# mm_robot_pcb_v4_1.net
KiCad netlist of a schematic drawn in EAGLE
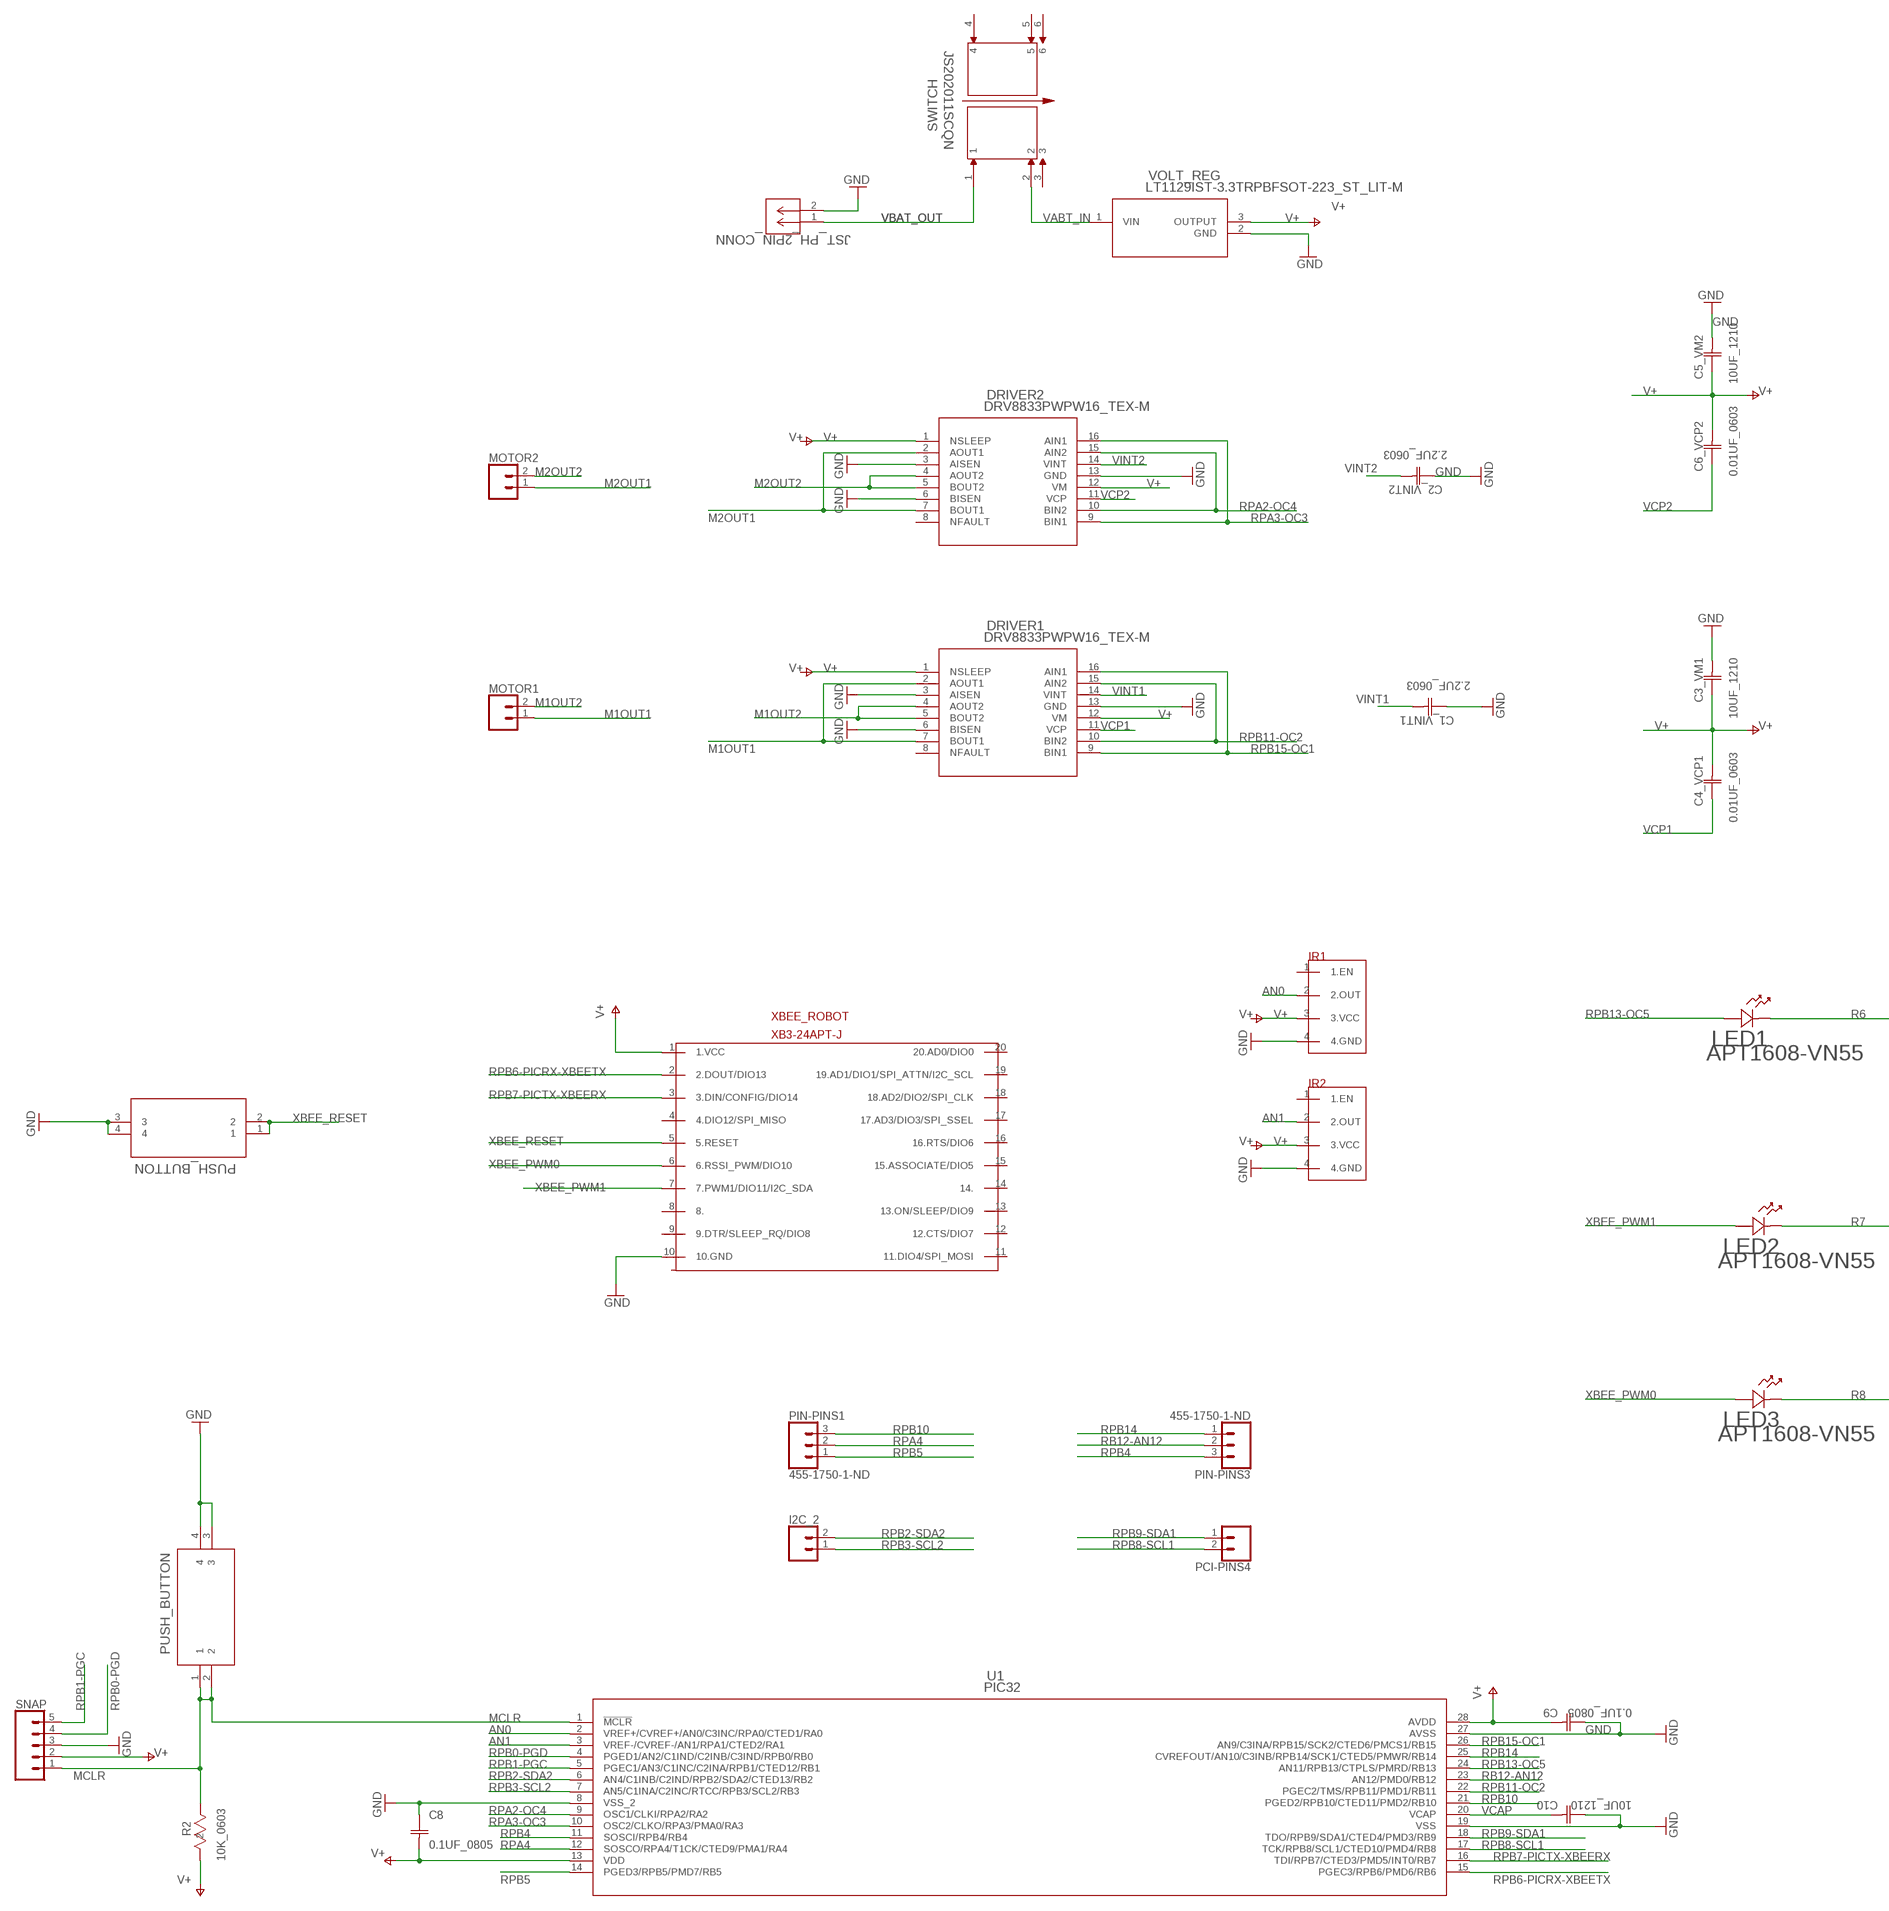
[diagram p0: schematic, sheet 1, part 1 of 2]
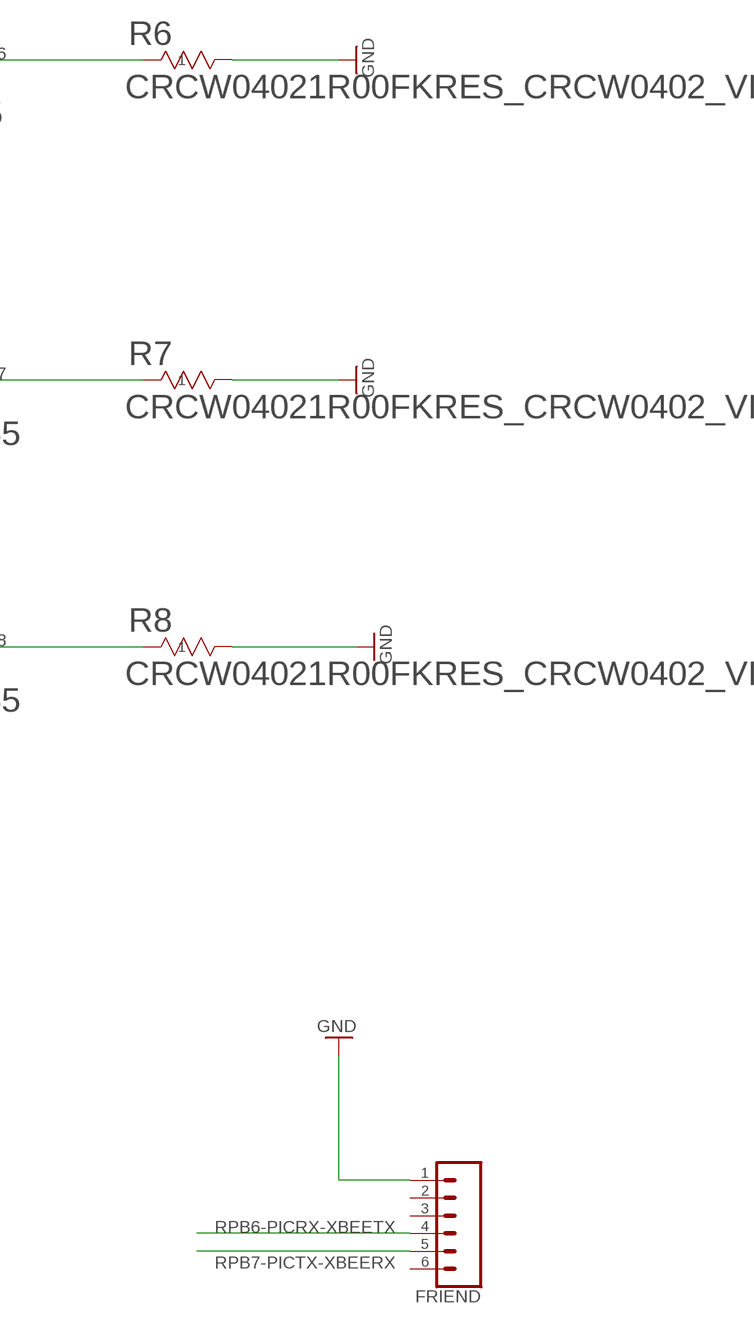
[diagram p1: schematic, sheet 1, part 2 of 2]

(export (version "E")
  (design (tool "Eeschema 10.0.6"))
  (components
    (comp (ref "C1_VINT1")
      (value "2.2UF_0603")
      (footprint "eagle-import:CAP_CL10_SAM-M")
      (fields
        (field (name "MANUFACTURER_PART_NUMBER") "CL10A225KP8NNNC")
        (field (name "COPYRIGHT") "Copyright (C) 2021 Ultra Librarian. All rights reserved.")
      )
      (libsource (lib "eagle-import") (part "CL10A225KP8NNNCCAP_CL10_SAM-M"))
    )
    (comp (ref "C2_VINT2")
      (value "2.2UF_0603")
      (footprint "eagle-import:CAP_CL10_SAM-M")
      (fields
        (field (name "MANUFACTURER_PART_NUMBER") "CL10A225KP8NNNC")
        (field (name "COPYRIGHT") "Copyright (C) 2021 Ultra Librarian. All rights reserved.")
      )
      (libsource (lib "eagle-import") (part "CL10A225KP8NNNCCAP_CL10_SAM-M"))
    )
    (comp (ref "C3_VM1")
      (value "10UF_1210")
      (footprint "eagle-import:CAP_TPS_B_AVX-M")
      (fields
        (field (name "MANUFACTURER_PART_NUMBER") "TPSB106K016R0500")
        (field (name "COPYRIGHT") "Copyright (C) 2021 Ultra Librarian. All rights reserved.")
      )
      (libsource (lib "eagle-import") (part "TPSB106K016R0500CAP_TPS_B_AVX-M"))
    )
    (comp (ref "C4_VCP1")
      (value "0.01UF_0603")
      (footprint "eagle-import:CAP_01UF_0603_X7R_G_AVX")
      (libsource (lib "eagle-import") (part "01UF_CAP"))
    )
    (comp (ref "C5_VM2")
      (value "10UF_1210")
      (footprint "eagle-import:CAP_TPS_B_AVX-M")
      (fields
        (field (name "MANUFACTURER_PART_NUMBER") "TPSB106K016R0500")
        (field (name "COPYRIGHT") "Copyright (C) 2021 Ultra Librarian. All rights reserved.")
      )
      (libsource (lib "eagle-import") (part "TPSB106K016R0500CAP_TPS_B_AVX-M"))
    )
    (comp (ref "C6_VCP2")
      (value "0.01UF_0603")
      (footprint "eagle-import:CAP_01UF_0603_X7R_G_AVX")
      (libsource (lib "eagle-import") (part "01UF_CAP"))
    )
    (comp (ref "C8")
      (value "0.1UF_0805")
      (footprint "eagle-import:CAP_C2012X7R2A104K125AA_TDK-M")
      (fields
        (field (name "MANUFACTURER_PART_NUMBER") "C2012X7R2A104K125AA")
        (field (name "COPYRIGHT") "Copyright (C) 2021 Ultra Librarian. All rights reserved.")
      )
      (libsource (lib "eagle-import") (part "C2012X7R2A104K125AACAP_C2012X7R2A104K125AA_TDK-M"))
    )
    (comp (ref "C9")
      (value "0.1UF_0805")
      (footprint "eagle-import:CAP_C2012X7R2A104K125AA_TDK-M")
      (fields
        (field (name "MANUFACTURER_PART_NUMBER") "C2012X7R2A104K125AA")
        (field (name "COPYRIGHT") "Copyright (C) 2021 Ultra Librarian. All rights reserved.")
      )
      (libsource (lib "eagle-import") (part "C2012X7R2A104K125AACAP_C2012X7R2A104K125AA_TDK-M"))
    )
    (comp (ref "C10")
      (value "10UF_1210")
      (footprint "eagle-import:CAP_TPS_B_AVX-M")
      (fields
        (field (name "MANUFACTURER_PART_NUMBER") "TPSB106K016R0500")
        (field (name "COPYRIGHT") "Copyright (C) 2021 Ultra Librarian. All rights reserved.")
      )
      (libsource (lib "eagle-import") (part "TPSB106K016R0500CAP_TPS_B_AVX-M"))
    )
    (comp (ref "DRIVER1")
      (value "DRV8833PWPW16_TEX-M")
      (footprint "eagle-import:PW16_TEX-M")
      (fields
        (field (name "MANUFACTURER_PART_NUMBER") "DRV8833PW")
        (field (name "COPYRIGHT") "Copyright (C) 2021 Ultra Librarian. All rights reserved.")
      )
      (libsource (lib "eagle-import") (part "DRV8833PWPW16_TEX-M"))
    )
    (comp (ref "DRIVER2")
      (value "DRV8833PWPW16_TEX-M")
      (footprint "eagle-import:PW16_TEX-M")
      (fields
        (field (name "MANUFACTURER_PART_NUMBER") "DRV8833PW")
        (field (name "COPYRIGHT") "Copyright (C) 2021 Ultra Librarian. All rights reserved.")
      )
      (libsource (lib "eagle-import") (part "DRV8833PWPW16_TEX-M"))
    )
    (comp (ref "FRIEND")
      (value "CONN_06NO_SILK_FEMALE_PTH")
      (footprint "eagle-import:1X06_NO_SILK")
      (libsource (lib "eagle-import") (part "CONN_06NO_SILK_FEMALE_PTH"))
    )
    (comp (ref "I2C_2")
      (value "CONN_02")
      (footprint "eagle-import:1X02")
      (libsource (lib "eagle-import") (part "CONN_02"))
    )
    (comp (ref "IR1")
      (value "GP2Y0A60SZLF")
      (footprint "eagle-import:1X04")
      (libsource (lib "eagle-import") (part "GP2Y0A60SZLF"))
    )
    (comp (ref "IR2")
      (value "GP2Y0A60SZLF")
      (footprint "eagle-import:1X04")
      (libsource (lib "eagle-import") (part "GP2Y0A60SZLF"))
    )
    (comp (ref "JST_PH_2PIN_CONN")
      (value "1769")
      (footprint "eagle-import:CONN_1769_ADA")
      (fields (field (name "COPYRIGHT") "Copyright (C) 2021 Ultra Librarian. All rights reserved."))
      (libsource (lib "eagle-import") (part "1769"))
    )
    (comp (ref "LED1")
      (value "APT1608-VN55")
      (footprint "eagle-import:LED_APT1608_KNB")
      (fields (field (name "COPYRIGHT") "Copyright (C) 2021 Ultra Librarian. All rights reserved."))
      (libsource (lib "eagle-import") (part "APT1608-VN55"))
    )
    (comp (ref "LED2")
      (value "APT1608-VN55")
      (footprint "eagle-import:LED_APT1608_KNB")
      (fields (field (name "COPYRIGHT") "Copyright (C) 2021 Ultra Librarian. All rights reserved."))
      (libsource (lib "eagle-import") (part "APT1608-VN55"))
    )
    (comp (ref "LED3")
      (value "APT1608-VN55")
      (footprint "eagle-import:LED_APT1608_KNB")
      (fields (field (name "COPYRIGHT") "Copyright (C) 2021 Ultra Librarian. All rights reserved."))
      (libsource (lib "eagle-import") (part "APT1608-VN55"))
    )
    (comp (ref "MOTOR1")
      (value "CONN_02")
      (footprint "eagle-import:1X02")
      (libsource (lib "eagle-import") (part "CONN_02"))
    )
    (comp (ref "MOTOR2")
      (value "CONN_02")
      (footprint "eagle-import:1X02")
      (libsource (lib "eagle-import") (part "CONN_02"))
    )
    (comp (ref "PCI-PINS4")
      (value "CONN_02")
      (footprint "eagle-import:1X02")
      (libsource (lib "eagle-import") (part "CONN_02"))
    )
    (comp (ref "PIC_PB")
      (value "PUSH_BUTTON")
      (footprint "eagle-import:SMT_FS-M")
      (fields
        (field (name "MANUFACTURER_PART_NUMBER") "PTS526 SK15 SMTR2 LFS")
        (field (name "COPYRIGHT") "Copyright (C) 2021 Ultra Librarian. All rights reserved.")
      )
      (libsource (lib "eagle-import") (part "PTS526_SK15_SMTR2_LFSSMT_FS-M"))
    )
    (comp (ref "PIN-PINS1")
      (value "455-1750-1-ND")
      (footprint "eagle-import:1X03")
      (libsource (lib "eagle-import") (part "CONN_03"))
    )
    (comp (ref "PIN-PINS3")
      (value "455-1750-1-ND")
      (footprint "eagle-import:1X03")
      (libsource (lib "eagle-import") (part "CONN_03"))
    )
    (comp (ref "R2")
      (value "10K_0603")
      (footprint "eagle-import:RES0603_CRG_TYCO_TYC-M")
      (fields
        (field (name "MANUFACTURER_PART_NUMBER") "CRG0603F10K")
        (field (name "COPYRIGHT") "Copyright (C) 2021 Ultra Librarian. All rights reserved.")
      )
      (libsource (lib "eagle-import") (part "CRG0603F10KRES0603_CRG_TYCO_TYC-M"))
    )
    (comp (ref "R6")
      (value "CRCW04021R00FKRES_CRCW0402_VIS-M")
      (footprint "eagle-import:RES_CRCW0402_VIS-M")
      (fields
        (field (name "MANUFACTURER_PART_NUMBER") "CRCW04021R00FK")
        (field (name "COPYRIGHT") "Copyright (C) 2021 Ultra Librarian. All rights reserved.")
      )
      (libsource (lib "eagle-import") (part "CRCW04021R00FKRES_CRCW0402_VIS-M"))
    )
    (comp (ref "R7")
      (value "CRCW04021R00FKRES_CRCW0402_VIS-M")
      (footprint "eagle-import:RES_CRCW0402_VIS-M")
      (fields
        (field (name "MANUFACTURER_PART_NUMBER") "CRCW04021R00FK")
        (field (name "COPYRIGHT") "Copyright (C) 2021 Ultra Librarian. All rights reserved.")
      )
      (libsource (lib "eagle-import") (part "CRCW04021R00FKRES_CRCW0402_VIS-M"))
    )
    (comp (ref "R8")
      (value "CRCW04021R00FKRES_CRCW0402_VIS-M")
      (footprint "eagle-import:RES_CRCW0402_VIS-M")
      (fields
        (field (name "MANUFACTURER_PART_NUMBER") "CRCW04021R00FK")
        (field (name "COPYRIGHT") "Copyright (C) 2021 Ultra Librarian. All rights reserved.")
      )
      (libsource (lib "eagle-import") (part "CRCW04021R00FKRES_CRCW0402_VIS-M"))
    )
    (comp (ref "SNAP")
      (value "CONN_05")
      (footprint "eagle-import:1X05")
      (libsource (lib "eagle-import") (part "CONN_05"))
    )
    (comp (ref "SWITCH")
      (value "JS202011SCQN")
      (footprint "eagle-import:SW_JS202011SCQN")
      (fields (field (name "COPYRIGHT") "Copyright (C) 2021 Ultra Librarian. All rights reserved."))
      (libsource (lib "eagle-import") (part "JS202011SCQN"))
    )
    (comp (ref "U1")
      (value "PIC32")
      (footprint "eagle-import:SSOP28_MC_MCH-M")
      (fields
        (field (name "MANUFACTURER_PART_NUMBER") "PIC32MX170F256B-I/SS")
        (field (name "COPYRIGHT") "Copyright (C) 2021 Ultra Librarian. All rights reserved.")
      )
      (libsource (lib "eagle-import") (part "PIC32MX170F256B-I/SSSSOP28_MC_MCH-M"))
    )
    (comp (ref "VOLT_REG")
      (value "LT1129IST-3.3TRPBFSOT-223_ST_LIT-M")
      (footprint "eagle-import:SOT-223_ST_LIT-M")
      (fields
        (field (name "MANUFACTURER_PART_NUMBER") "LT1129IST-3.3#TRPBF")
        (field (name "COPYRIGHT") "Copyright (C) 2021 Ultra Librarian. All rights reserved.")
      )
      (libsource (lib "eagle-import") (part "LT1129IST-3.3TRPBFSOT-223_ST_LIT-M"))
    )
    (comp (ref "XBEE_PB")
      (value "PUSH_BUTTON")
      (footprint "eagle-import:SMT_FS-M")
      (fields
        (field (name "MANUFACTURER_PART_NUMBER") "PTS526 SK15 SMTR2 LFS")
        (field (name "COPYRIGHT") "Copyright (C) 2021 Ultra Librarian. All rights reserved.")
      )
      (libsource (lib "eagle-import") (part "PTS526_SK15_SMTR2_LFSSMT_FS-M"))
    )
    (comp (ref "XBEE_ROBOT")
      (value "XB3-24APT-J")
      (footprint "eagle-import:XB3-24APT-J")
      (libsource (lib "eagle-import") (part "XB3-24APT-J"))
    )
  )
  (nets
    (net (code "1") (name "/AN0") (class "Default")
      (node (ref "IR1") (pin "2") (pinfunction "2.OUT_2") (pintype "bidirectional"))
      (node (ref "U1") (pin "2") (pinfunction "VREF+/CVREF+/AN0/C3INC/RPA0/CTED1/RA0_2") (pintype "bidirectional"))
    )
    (net (code "2") (name "/AN1") (class "Default")
      (node (ref "IR2") (pin "2") (pinfunction "2.OUT_2") (pintype "bidirectional"))
      (node (ref "U1") (pin "3") (pinfunction "VREF-/CVREF-/AN1/RPA1/CTED2/RA1_3") (pintype "bidirectional"))
    )
    (net (code "3") (name "/M1OUT1") (class "Default")
      (node (ref "DRIVER1") (pin "2") (pinfunction "AOUT1_2") (pintype "output"))
      (node (ref "DRIVER1") (pin "7") (pinfunction "BOUT1_7") (pintype "output"))
      (node (ref "MOTOR1") (pin "1") (pinfunction "1_1") (pintype "passive"))
    )
    (net (code "4") (name "/M1OUT2") (class "Default")
      (node (ref "DRIVER1") (pin "4") (pinfunction "AOUT2_4") (pintype "output"))
      (node (ref "DRIVER1") (pin "5") (pinfunction "BOUT2_5") (pintype "output"))
      (node (ref "MOTOR1") (pin "2") (pinfunction "2_2") (pintype "passive"))
    )
    (net (code "5") (name "/M2OUT1") (class "Default")
      (node (ref "DRIVER2") (pin "2") (pinfunction "AOUT1_2") (pintype "output"))
      (node (ref "DRIVER2") (pin "7") (pinfunction "BOUT1_7") (pintype "output"))
      (node (ref "MOTOR2") (pin "1") (pinfunction "1_1") (pintype "passive"))
    )
    (net (code "6") (name "/M2OUT2") (class "Default")
      (node (ref "DRIVER2") (pin "4") (pinfunction "AOUT2_4") (pintype "output"))
      (node (ref "DRIVER2") (pin "5") (pinfunction "BOUT2_5") (pintype "output"))
      (node (ref "MOTOR2") (pin "2") (pinfunction "2_2") (pintype "passive"))
    )
    (net (code "7") (name "/MCLR") (class "Default")
      (node (ref "PIC_PB") (pin "1") (pinfunction "1_1") (pintype "passive"))
      (node (ref "PIC_PB") (pin "2") (pinfunction "2_2") (pintype "passive"))
      (node (ref "R2") (pin "1") (pinfunction "1_1") (pintype "passive"))
      (node (ref "SNAP") (pin "1") (pinfunction "1_1") (pintype "passive"))
      (node (ref "U1") (pin "1") (pinfunction "~{MCLR}_1") (pintype "bidirectional"))
    )
    (net (code "8") (name "/R6") (class "Default")
      (node (ref "LED1") (pin "1") (pinfunction "1_1") (pintype "passive"))
      (node (ref "R6") (pin "1") (pinfunction "1_1") (pintype "passive"))
    )
    (net (code "9") (name "/R7") (class "Default")
      (node (ref "LED2") (pin "1") (pinfunction "1_1") (pintype "passive"))
      (node (ref "R7") (pin "1") (pinfunction "1_1") (pintype "passive"))
    )
    (net (code "10") (name "/R8") (class "Default")
      (node (ref "LED3") (pin "1") (pinfunction "1_1") (pintype "passive"))
      (node (ref "R8") (pin "1") (pinfunction "1_1") (pintype "passive"))
    )
    (net (code "11") (name "/RB12-AN12") (class "Default")
      (node (ref "PIN-PINS3") (pin "2") (pinfunction "2_2") (pintype "passive"))
      (node (ref "U1") (pin "23") (pinfunction "AN12/PMD0/RB12_23") (pintype "bidirectional"))
    )
    (net (code "12") (name "/RPA2-OC4") (class "Default")
      (node (ref "DRIVER2") (pin "10") (pinfunction "BIN2_10") (pintype "input"))
      (node (ref "DRIVER2") (pin "15") (pinfunction "AIN2_15") (pintype "input"))
      (node (ref "U1") (pin "9") (pinfunction "OSC1/CLKI/RPA2/RA2_9") (pintype "bidirectional"))
    )
    (net (code "13") (name "/RPA3-OC3") (class "Default")
      (node (ref "DRIVER2") (pin "16") (pinfunction "AIN1_16") (pintype "input"))
      (node (ref "DRIVER2") (pin "9") (pinfunction "BIN1_9") (pintype "input"))
      (node (ref "U1") (pin "10") (pinfunction "OSC2/CLKO/RPA3/PMA0/RA3_10") (pintype "bidirectional"))
    )
    (net (code "14") (name "/RPA4") (class "Default")
      (node (ref "PIN-PINS1") (pin "2") (pinfunction "2_2") (pintype "passive"))
      (node (ref "U1") (pin "12") (pinfunction "SOSCO/RPA4/T1CK/CTED9/PMA1/RA4_12") (pintype "bidirectional"))
    )
    (net (code "15") (name "/RPB0-PGD") (class "Default")
      (node (ref "SNAP") (pin "4") (pinfunction "4_4") (pintype "passive"))
      (node (ref "U1") (pin "4") (pinfunction "PGED1/AN2/C1IND/C2INB/C3IND/RPB0/RB0_4") (pintype "bidirectional"))
    )
    (net (code "16") (name "/RPB1-PGC") (class "Default")
      (node (ref "SNAP") (pin "5") (pinfunction "5_5") (pintype "passive"))
      (node (ref "U1") (pin "5") (pinfunction "PGEC1/AN3/C1INC/C2INA/RPB1/CTED12/RB1_5") (pintype "bidirectional"))
    )
    (net (code "17") (name "/RPB2-SDA2") (class "Default")
      (node (ref "I2C_2") (pin "2") (pinfunction "2_2") (pintype "passive"))
      (node (ref "U1") (pin "6") (pinfunction "AN4/C1INB/C2IND/RPB2/SDA2/CTED13/RB2_6") (pintype "bidirectional"))
    )
    (net (code "18") (name "/RPB3-SCL2") (class "Default")
      (node (ref "I2C_2") (pin "1") (pinfunction "1_1") (pintype "passive"))
      (node (ref "U1") (pin "7") (pinfunction "AN5/C1INA/C2INC/RTCC/RPB3/SCL2/RB3_7") (pintype "bidirectional"))
    )
    (net (code "19") (name "/RPB4") (class "Default")
      (node (ref "PIN-PINS3") (pin "3") (pinfunction "3_3") (pintype "passive"))
      (node (ref "U1") (pin "11") (pinfunction "SOSCI/RPB4/RB4_11") (pintype "bidirectional"))
    )
    (net (code "20") (name "/RPB5") (class "Default")
      (node (ref "PIN-PINS1") (pin "1") (pinfunction "1_1") (pintype "passive"))
      (node (ref "U1") (pin "14") (pinfunction "PGED3/RPB5/PMD7/RB5_14") (pintype "bidirectional"))
    )
    (net (code "21") (name "/RPB6-PICRX-XBEETX") (class "Default")
      (node (ref "FRIEND") (pin "4") (pinfunction "4_4") (pintype "passive"))
      (node (ref "U1") (pin "15") (pinfunction "PGEC3/RPB6/PMD6/RB6_15") (pintype "bidirectional"))
      (node (ref "XBEE_ROBOT") (pin "2") (pinfunction "2.DOUT/DIO13_2") (pintype "bidirectional"))
    )
    (net (code "22") (name "/RPB7-PICTX-XBEERX") (class "Default")
      (node (ref "FRIEND") (pin "5") (pinfunction "5_5") (pintype "passive"))
      (node (ref "U1") (pin "16") (pinfunction "TDI/RPB7/CTED3/PMD5/INT0/RB7_16") (pintype "bidirectional"))
      (node (ref "XBEE_ROBOT") (pin "3") (pinfunction "3.DIN/CONFIG/DIO14_3") (pintype "bidirectional"))
    )
    (net (code "23") (name "/RPB8-SCL1") (class "Default")
      (node (ref "PCI-PINS4") (pin "2") (pinfunction "2_2") (pintype "passive"))
      (node (ref "U1") (pin "17") (pinfunction "TCK/RPB8/SCL1/CTED10/PMD4/RB8_17") (pintype "bidirectional"))
    )
    (net (code "24") (name "/RPB9-SDA1") (class "Default")
      (node (ref "PCI-PINS4") (pin "1") (pinfunction "1_1") (pintype "passive"))
      (node (ref "U1") (pin "18") (pinfunction "TDO/RPB9/SDA1/CTED4/PMD3/RB9_18") (pintype "bidirectional"))
    )
    (net (code "25") (name "/RPB10") (class "Default")
      (node (ref "PIN-PINS1") (pin "3") (pinfunction "3_3") (pintype "passive"))
      (node (ref "U1") (pin "21") (pinfunction "PGED2/RPB10/CTED11/PMD2/RB10_21") (pintype "bidirectional"))
    )
    (net (code "26") (name "/RPB11-OC2") (class "Default")
      (node (ref "DRIVER1") (pin "10") (pinfunction "BIN2_10") (pintype "input"))
      (node (ref "DRIVER1") (pin "15") (pinfunction "AIN2_15") (pintype "input"))
      (node (ref "U1") (pin "22") (pinfunction "PGEC2/TMS/RPB11/PMD1/RB11_22") (pintype "bidirectional"))
    )
    (net (code "27") (name "/RPB13-OC5") (class "Default")
      (node (ref "LED1") (pin "2") (pinfunction "2_2") (pintype "passive"))
      (node (ref "U1") (pin "24") (pinfunction "AN11/RPB13/CTPLS/PMRD/RB13_24") (pintype "bidirectional"))
    )
    (net (code "28") (name "/RPB14") (class "Default")
      (node (ref "PIN-PINS3") (pin "1") (pinfunction "1_1") (pintype "passive"))
      (node (ref "U1") (pin "25") (pinfunction "CVREFOUT/AN10/C3INB/RPB14/SCK1/CTED5/PMWR/RB14_25") (pintype "bidirectional"))
    )
    (net (code "29") (name "/RPB15-OC1") (class "Default")
      (node (ref "DRIVER1") (pin "16") (pinfunction "AIN1_16") (pintype "input"))
      (node (ref "DRIVER1") (pin "9") (pinfunction "BIN1_9") (pintype "input"))
      (node (ref "U1") (pin "26") (pinfunction "AN9/C3INA/RPB15/SCK2/CTED6/PMCS1/RB15_26") (pintype "bidirectional"))
    )
    (net (code "30") (name "/VABT_IN") (class "Default")
      (node (ref "SWITCH") (pin "2") (pinfunction "2_2") (pintype "passive"))
      (node (ref "VOLT_REG") (pin "1") (pinfunction "VIN_1") (pintype "input"))
    )
    (net (code "31") (name "/VBAT_OUT") (class "Default")
      (node (ref "JST_PH_2PIN_CONN") (pin "1") (pinfunction "1_1") (pintype "passive"))
      (node (ref "SWITCH") (pin "1") (pinfunction "1_1") (pintype "passive"))
    )
    (net (code "32") (name "/VCAP") (class "Default")
      (node (ref "C10") (pin "2") (pinfunction "12_2") (pintype "passive"))
      (node (ref "U1") (pin "20") (pinfunction "VCAP_20") (pintype "power_in"))
    )
    (net (code "33") (name "/VCP1") (class "Default")
      (node (ref "C4_VCP1") (pin "1") (pinfunction "1_1") (pintype "passive"))
      (node (ref "DRIVER1") (pin "11") (pinfunction "VCP_11") (pintype "bidirectional"))
    )
    (net (code "34") (name "/VCP2") (class "Default")
      (node (ref "C6_VCP2") (pin "1") (pinfunction "1_1") (pintype "passive"))
      (node (ref "DRIVER2") (pin "11") (pinfunction "VCP_11") (pintype "bidirectional"))
    )
    (net (code "35") (name "/VINT1") (class "Default")
      (node (ref "C1_VINT1") (pin "2") (pinfunction "2_2") (pintype "passive"))
      (node (ref "DRIVER1") (pin "14") (pinfunction "VINT_14") (pintype "passive"))
    )
    (net (code "36") (name "/VINT2") (class "Default")
      (node (ref "C2_VINT2") (pin "2") (pinfunction "2_2") (pintype "passive"))
      (node (ref "DRIVER2") (pin "14") (pinfunction "VINT_14") (pintype "passive"))
    )
    (net (code "37") (name "/XBEE_PWM0") (class "Default")
      (node (ref "LED3") (pin "2") (pinfunction "2_2") (pintype "passive"))
      (node (ref "XBEE_ROBOT") (pin "6") (pinfunction "6.RSSI_PWM/DIO10_6") (pintype "bidirectional"))
    )
    (net (code "38") (name "/XBEE_PWM1") (class "Default")
      (node (ref "LED2") (pin "2") (pinfunction "2_2") (pintype "passive"))
      (node (ref "XBEE_ROBOT") (pin "7") (pinfunction "7.PWM1/DIO11/I2C_SDA_7") (pintype "bidirectional"))
    )
    (net (code "39") (name "/XBEE_RESET") (class "Default")
      (node (ref "XBEE_PB") (pin "1") (pinfunction "1_1") (pintype "passive"))
      (node (ref "XBEE_PB") (pin "2") (pinfunction "2_2") (pintype "passive"))
      (node (ref "XBEE_ROBOT") (pin "5") (pinfunction "5.RESET_5") (pintype "bidirectional"))
    )
    (net (code "40") (name "GND") (class "Default")
      (node (ref "C10") (pin "1") (pinfunction "11_1") (pintype "passive"))
      (node (ref "C1_VINT1") (pin "1") (pinfunction "1_1") (pintype "passive"))
      (node (ref "C2_VINT2") (pin "1") (pinfunction "1_1") (pintype "passive"))
      (node (ref "C3_VM1") (pin "2") (pinfunction "12_2") (pintype "passive"))
      (node (ref "C5_VM2") (pin "2") (pinfunction "12_2") (pintype "passive"))
      (node (ref "C8") (pin "1") (pinfunction "1_1") (pintype "passive"))
      (node (ref "C9") (pin "1") (pinfunction "1_1") (pintype "passive"))
      (node (ref "DRIVER1") (pin "13") (pinfunction "GND_13") (pintype "power_in"))
      (node (ref "DRIVER1") (pin "3") (pinfunction "AISEN_3") (pintype "bidirectional"))
      (node (ref "DRIVER1") (pin "6") (pinfunction "BISEN_6") (pintype "bidirectional"))
      (node (ref "DRIVER2") (pin "13") (pinfunction "GND_13") (pintype "power_in"))
      (node (ref "DRIVER2") (pin "3") (pinfunction "AISEN_3") (pintype "bidirectional"))
      (node (ref "DRIVER2") (pin "6") (pinfunction "BISEN_6") (pintype "bidirectional"))
      (node (ref "FRIEND") (pin "1") (pinfunction "1_1") (pintype "passive"))
      (node (ref "IR1") (pin "4") (pinfunction "4.GND_4") (pintype "bidirectional"))
      (node (ref "IR2") (pin "4") (pinfunction "4.GND_4") (pintype "bidirectional"))
      (node (ref "JST_PH_2PIN_CONN") (pin "2") (pinfunction "2_2") (pintype "passive"))
      (node (ref "PIC_PB") (pin "3") (pinfunction "3_3") (pintype "passive"))
      (node (ref "PIC_PB") (pin "4") (pinfunction "4_4") (pintype "passive"))
      (node (ref "R6") (pin "2") (pinfunction "2_2") (pintype "passive"))
      (node (ref "R7") (pin "2") (pinfunction "2_2") (pintype "passive"))
      (node (ref "R8") (pin "2") (pinfunction "2_2") (pintype "passive"))
      (node (ref "SNAP") (pin "3") (pinfunction "3_3") (pintype "passive"))
      (node (ref "U1") (pin "19") (pinfunction "VSS_19") (pintype "power_in"))
      (node (ref "U1") (pin "27") (pinfunction "AVSS_27") (pintype "power_in"))
      (node (ref "U1") (pin "8") (pinfunction "VSS_2_8") (pintype "power_in"))
      (node (ref "VOLT_REG") (pin "2") (pinfunction "GND_2") (pintype "power_in"))
      (node (ref "XBEE_PB") (pin "3") (pinfunction "3_3") (pintype "passive"))
      (node (ref "XBEE_PB") (pin "4") (pinfunction "4_4") (pintype "passive"))
      (node (ref "XBEE_ROBOT") (pin "10") (pinfunction "10.GND_10") (pintype "bidirectional"))
    )
    (net (code "41") (name "V+") (class "Default")
      (node (ref "C3_VM1") (pin "1") (pinfunction "11_1") (pintype "passive"))
      (node (ref "C4_VCP1") (pin "2") (pinfunction "2_2") (pintype "passive"))
      (node (ref "C5_VM2") (pin "1") (pinfunction "11_1") (pintype "passive"))
      (node (ref "C6_VCP2") (pin "2") (pinfunction "2_2") (pintype "passive"))
      (node (ref "C8") (pin "2") (pinfunction "2_2") (pintype "passive"))
      (node (ref "C9") (pin "2") (pinfunction "2_2") (pintype "passive"))
      (node (ref "DRIVER1") (pin "1") (pinfunction "NSLEEP_1") (pintype "input"))
      (node (ref "DRIVER1") (pin "12") (pinfunction "VM_12") (pintype "power_in"))
      (node (ref "DRIVER2") (pin "1") (pinfunction "NSLEEP_1") (pintype "input"))
      (node (ref "DRIVER2") (pin "12") (pinfunction "VM_12") (pintype "power_in"))
      (node (ref "IR1") (pin "3") (pinfunction "3.VCC_3") (pintype "bidirectional"))
      (node (ref "IR2") (pin "3") (pinfunction "3.VCC_3") (pintype "bidirectional"))
      (node (ref "R2") (pin "2") (pinfunction "2_2") (pintype "passive"))
      (node (ref "SNAP") (pin "2") (pinfunction "2_2") (pintype "passive"))
      (node (ref "U1") (pin "13") (pinfunction "VDD_13") (pintype "power_in"))
      (node (ref "U1") (pin "28") (pinfunction "AVDD_28") (pintype "power_in"))
      (node (ref "VOLT_REG") (pin "3") (pinfunction "OUTPUT_3") (pintype "output"))
      (node (ref "XBEE_ROBOT") (pin "1") (pinfunction "1.VCC_1") (pintype "bidirectional"))
    )
    (net (code "42") (name "unconnected-(DRIVER1-NFAULT-Pad8)") (class "Default")
      (node (ref "DRIVER1") (pin "8") (pinfunction "NFAULT_8") (pintype "output"))
    )
    (net (code "43") (name "unconnected-(DRIVER2-NFAULT-Pad8)") (class "Default")
      (node (ref "DRIVER2") (pin "8") (pinfunction "NFAULT_8") (pintype "output"))
    )
    (net (code "44") (name "unconnected-(FRIEND-Pad2)") (class "Default")
      (node (ref "FRIEND") (pin "2") (pinfunction "2_2") (pintype "passive"))
    )
    (net (code "45") (name "unconnected-(FRIEND-Pad3)") (class "Default")
      (node (ref "FRIEND") (pin "3") (pinfunction "3_3") (pintype "passive"))
    )
    (net (code "46") (name "unconnected-(FRIEND-Pad6)") (class "Default")
      (node (ref "FRIEND") (pin "6") (pinfunction "6_6") (pintype "passive"))
    )
    (net (code "47") (name "unconnected-(IR1-1.EN-Pad1)") (class "Default")
      (node (ref "IR1") (pin "1") (pinfunction "1.EN_1") (pintype "bidirectional"))
    )
    (net (code "48") (name "unconnected-(IR2-1.EN-Pad1)") (class "Default")
      (node (ref "IR2") (pin "1") (pinfunction "1.EN_1") (pintype "bidirectional"))
    )
    (net (code "49") (name "unconnected-(SWITCH-Pad3)") (class "Default")
      (node (ref "SWITCH") (pin "3") (pinfunction "3_3") (pintype "passive"))
    )
    (net (code "50") (name "unconnected-(SWITCH-Pad4)") (class "Default")
      (node (ref "SWITCH") (pin "4") (pinfunction "4_4") (pintype "passive"))
    )
    (net (code "51") (name "unconnected-(SWITCH-Pad5)") (class "Default")
      (node (ref "SWITCH") (pin "5") (pinfunction "5_5") (pintype "passive"))
    )
    (net (code "52") (name "unconnected-(SWITCH-Pad6)") (class "Default")
      (node (ref "SWITCH") (pin "6") (pinfunction "6_6") (pintype "passive"))
    )
    (net (code "53") (name "unconnected-(XBEE_ROBOT-4.DIO12{slash}SPI_MISO-Pad4)") (class "Default")
      (node (ref "XBEE_ROBOT") (pin "4") (pinfunction "4.DIO12/SPI_MISO_4") (pintype "bidirectional"))
    )
    (net (code "54") (name "unconnected-(XBEE_ROBOT-8.-Pad8)") (class "Default")
      (node (ref "XBEE_ROBOT") (pin "8") (pinfunction "8._8") (pintype "bidirectional"))
    )
    (net (code "55") (name "unconnected-(XBEE_ROBOT-9.DTR{slash}SLEEP_RQ{slash}DIO8-Pad9)") (class "Default")
      (node (ref "XBEE_ROBOT") (pin "9") (pinfunction "9.DTR/SLEEP_RQ/DIO8_9") (pintype "bidirectional"))
    )
    (net (code "56") (name "unconnected-(XBEE_ROBOT-11.DIO4{slash}SPI_MOSI-Pad11)") (class "Default")
      (node (ref "XBEE_ROBOT") (pin "11") (pinfunction "11.DIO4/SPI_MOSI_11") (pintype "bidirectional"))
    )
    (net (code "57") (name "unconnected-(XBEE_ROBOT-12.CTS{slash}DIO7-Pad12)") (class "Default")
      (node (ref "XBEE_ROBOT") (pin "12") (pinfunction "12.CTS/DIO7_12") (pintype "bidirectional"))
    )
    (net (code "58") (name "unconnected-(XBEE_ROBOT-13.ON{slash}SLEEP{slash}DIO9-Pad13)") (class "Default")
      (node (ref "XBEE_ROBOT") (pin "13") (pinfunction "13.ON/SLEEP/DIO9_13") (pintype "bidirectional"))
    )
    (net (code "59") (name "unconnected-(XBEE_ROBOT-14.-Pad14)") (class "Default")
      (node (ref "XBEE_ROBOT") (pin "14") (pinfunction "14._14") (pintype "bidirectional"))
    )
    (net (code "60") (name "unconnected-(XBEE_ROBOT-15.ASSOCIATE{slash}DIO5-Pad15)") (class "Default")
      (node (ref "XBEE_ROBOT") (pin "15") (pinfunction "15.ASSOCIATE/DIO5_15") (pintype "bidirectional"))
    )
    (net (code "61") (name "unconnected-(XBEE_ROBOT-16.RTS{slash}DIO6-Pad16)") (class "Default")
      (node (ref "XBEE_ROBOT") (pin "16") (pinfunction "16.RTS/DIO6_16") (pintype "bidirectional"))
    )
    (net (code "62") (name "unconnected-(XBEE_ROBOT-17.AD3{slash}DIO3{slash}SPI_SSEL-Pad17)") (class "Default")
      (node (ref "XBEE_ROBOT") (pin "17") (pinfunction "17.AD3/DIO3/SPI_SSEL_17") (pintype "bidirectional"))
    )
    (net (code "63") (name "unconnected-(XBEE_ROBOT-18.AD2{slash}DIO2{slash}SPI_CLK-Pad18)") (class "Default")
      (node (ref "XBEE_ROBOT") (pin "18") (pinfunction "18.AD2/DIO2/SPI_CLK_18") (pintype "bidirectional"))
    )
    (net (code "64") (name "unconnected-(XBEE_ROBOT-19.AD1{slash}DIO1{slash}SPI_ATTN{slash}I2C_SCL-Pad19)") (class "Default")
      (node (ref "XBEE_ROBOT") (pin "19") (pinfunction "19.AD1/DIO1/SPI_ATTN/I2C_SCL_19") (pintype "bidirectional"))
    )
    (net (code "65") (name "unconnected-(XBEE_ROBOT-20.AD0{slash}DIO0-Pad20)") (class "Default")
      (node (ref "XBEE_ROBOT") (pin "20") (pinfunction "20.AD0/DIO0_20") (pintype "bidirectional"))
    )
  )
)
